# Thermistors.net
KiCad netlist of a schematic drawn in Altium Designer
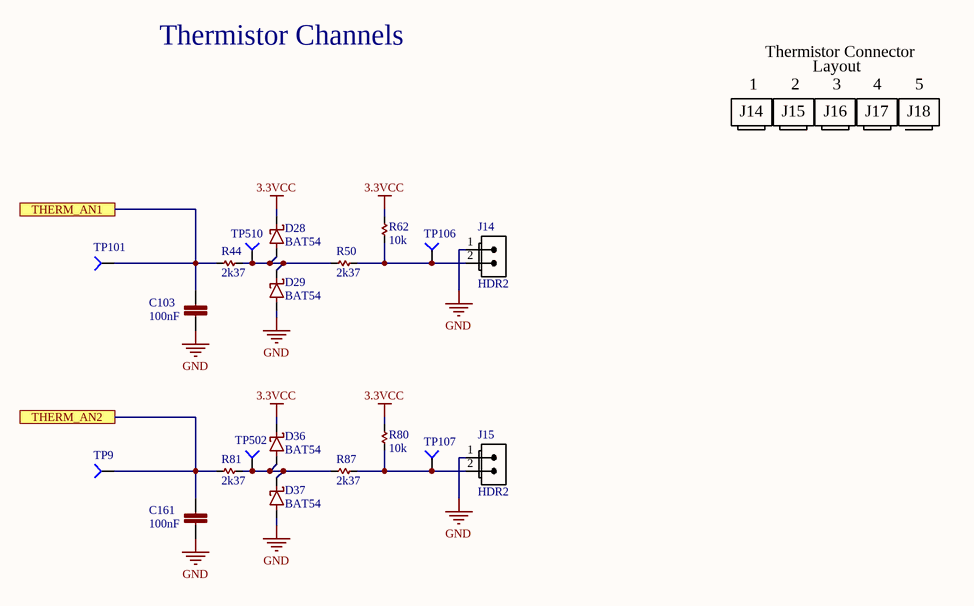
[diagram p0: Thermistors.SchDoc]

(export (version "E")
  (design (tool "Eeschema 10.0.6"))
  (components
    (comp (ref "C103")
      (value "100nF")
      (footprint "C0402")
      (description "CAP CER 0402 100nF 16V 10% X7R")
      (fields (field (name "MANUFACTURER") "Murata") (field (name "PART") "GRM155R71C104KA88D"))
      (libsource (lib "3Delight") (part "GRM155R71C104KA88D"))
    )
    (comp (ref "C161")
      (value "100nF")
      (footprint "C0402")
      (description "CAP CER 0402 100nF 16V 10% X7R")
      (fields (field (name "MANUFACTURER") "Murata") (field (name "PART") "GRM155R71C104KA88D"))
      (libsource (lib "3Delight") (part "GRM155R71C104KA88D"))
    )
    (comp (ref "D28")
      (value "BAT54")
      (footprint "SOD523_IPC")
      (description "DIODE SCHOTTKY 30V 200MA SOD523")
      (fields (field (name "MANUFACTURER") "Diodes Incorporated") (field (name "PART") "BAT54WX-TP"))
      (libsource (lib "Diodes") (part "BAT54WX"))
    )
    (comp (ref "D29")
      (value "BAT54")
      (footprint "SOD523_IPC")
      (description "DIODE SCHOTTKY 30V 200MA SOD523")
      (fields (field (name "MANUFACTURER") "Diodes Incorporated") (field (name "PART") "BAT54WX-TP"))
      (libsource (lib "Diodes") (part "BAT54WX"))
    )
    (comp (ref "D36")
      (value "BAT54")
      (footprint "SOD523_IPC")
      (description "DIODE SCHOTTKY 30V 200MA SOD523")
      (fields (field (name "MANUFACTURER") "Diodes Incorporated") (field (name "PART") "BAT54WX-TP"))
      (libsource (lib "Diodes") (part "BAT54WX"))
    )
    (comp (ref "D37")
      (value "BAT54")
      (footprint "SOD523_IPC")
      (description "DIODE SCHOTTKY 30V 200MA SOD523")
      (fields (field (name "MANUFACTURER") "Diodes Incorporated") (field (name "PART") "BAT54WX-TP"))
      (libsource (lib "Diodes") (part "BAT54WX"))
    )
    (comp (ref "J14")
      (value "HDR2")
      (footprint "70543-01 PIN-IN-PASTE")
      (description "Connector 2pos - Pin in Paste")
      (fields (field (name "MANUFACTURER") "Molex") (field (name "PART") "0705430001"))
      (libsource (lib "Connectors") (part "CONN 2PIN VERT 0.1{dblquote} SHRD LOCKING PIP"))
    )
    (comp (ref "J15")
      (value "HDR2")
      (footprint "70543-01 PIN-IN-PASTE")
      (description "Connector 2pos - Pin in Paste")
      (fields (field (name "MANUFACTURER") "Molex") (field (name "PART") "0705430001"))
      (libsource (lib "Connectors") (part "CONN 2PIN VERT 0.1{dblquote} SHRD LOCKING PIP"))
    )
    (comp (ref "R44")
      (value "2k37")
      (footprint "R0402")
      (description "RES SMD 2.37K OHM 1% 1/16W 0402")
      (fields (field (name "MANUFACTURER") "Yageo") (field (name "PART") "RC0402FR-072K37L"))
      (libsource (lib "3Delight") (part "RC0402FR-072K37L"))
    )
    (comp (ref "R50")
      (value "2k37")
      (footprint "R0402")
      (description "RES SMD 2.37K OHM 1% 1/16W 0402")
      (fields (field (name "MANUFACTURER") "Yageo") (field (name "PART") "RC0402FR-072K37L"))
      (libsource (lib "3Delight") (part "RC0402FR-072K37L"))
    )
    (comp (ref "R62")
      (value "10k")
      (footprint "R0402")
      (description "RES SMD 4.7K OHM 1% 1/16W 0402")
      (fields (field (name "MANUFACTURER") "YAGEO") (field (name "PART") "RC0402FR-074K7L"))
      (libsource (lib "3Delight") (part "RC0402FR-074K7L"))
    )
    (comp (ref "R80")
      (value "10k")
      (footprint "R0402")
      (description "RES SMD 4.7K OHM 1% 1/16W 0402")
      (fields (field (name "MANUFACTURER") "YAGEO") (field (name "PART") "RC0402FR-074K7L"))
      (libsource (lib "3Delight") (part "RC0402FR-074K7L"))
    )
    (comp (ref "R81")
      (value "2k37")
      (footprint "R0402")
      (description "RES SMD 2.37K OHM 1% 1/16W 0402")
      (fields (field (name "MANUFACTURER") "Yageo") (field (name "PART") "RC0402FR-072K37L"))
      (libsource (lib "3Delight") (part "RC0402FR-072K37L"))
    )
    (comp (ref "R87")
      (value "2k37")
      (footprint "R0402")
      (description "RES SMD 2.37K OHM 1% 1/16W 0402")
      (fields (field (name "MANUFACTURER") "Yageo") (field (name "PART") "RC0402FR-072K37L"))
      (libsource (lib "3Delight") (part "RC0402FR-072K37L"))
    )
    (comp (ref "TP9")
      (value "TP4")
      (footprint "TP-2")
      (description "Socket")
      (fields (field (name "PART") "NOTAPART-Testpoint"))
      (libsource (lib "Archim") (part "Socket"))
    )
    (comp (ref "TP101")
      (value "TP4")
      (footprint "TP-2")
      (description "Socket")
      (fields (field (name "PART") "NOTAPART-Testpoint"))
      (libsource (lib "Archim") (part "Socket"))
    )
    (comp (ref "TP106")
      (value "TP4")
      (footprint "TP-2")
      (description "Socket")
      (fields (field (name "PART") "NOTAPART-Testpoint"))
      (libsource (lib "Archim") (part "Socket"))
    )
    (comp (ref "TP107")
      (value "TP4")
      (footprint "TP-2")
      (description "Socket")
      (fields (field (name "PART") "NOTAPART-Testpoint"))
      (libsource (lib "Archim") (part "Socket"))
    )
    (comp (ref "TP502")
      (value "TP4")
      (footprint "TP-2")
      (description "Socket")
      (fields (field (name "PART") "NOTAPART-Testpoint"))
      (libsource (lib "Archim") (part "Socket"))
    )
    (comp (ref "TP510")
      (value "TP4")
      (footprint "TP-2")
      (description "Socket")
      (fields (field (name "PART") "NOTAPART-Testpoint"))
      (libsource (lib "Archim") (part "Socket"))
    )
  )
  (nets
    (net (code "1") (name "/THERM_AN1") (class "Default")
      (node (ref "C103") (pin "1") (pinfunction "1_1") (pintype "passive"))
      (node (ref "R44") (pin "1") (pinfunction "1_1") (pintype "passive"))
      (node (ref "TP101") (pin "1") (pinfunction "1_1") (pintype "passive"))
    )
    (net (code "2") (name "/THERM_AN2") (class "Default")
      (node (ref "C161") (pin "1") (pinfunction "1_1") (pintype "passive"))
      (node (ref "R81") (pin "1") (pinfunction "1_1") (pintype "passive"))
      (node (ref "TP9") (pin "1") (pinfunction "1_1") (pintype "passive"))
    )
    (net (code "3") (name "3.3VCC") (class "Default")
      (node (ref "D28") (pin "K") (pinfunction "K_K") (pintype "passive"))
      (node (ref "D36") (pin "K") (pinfunction "K_K") (pintype "passive"))
      (node (ref "R62") (pin "2") (pinfunction "2_2") (pintype "passive"))
      (node (ref "R80") (pin "2") (pinfunction "2_2") (pintype "passive"))
    )
    (net (code "4") (name "GND") (class "Default")
      (node (ref "C103") (pin "2") (pinfunction "2_2") (pintype "passive"))
      (node (ref "C161") (pin "2") (pinfunction "2_2") (pintype "passive"))
      (node (ref "D29") (pin "A") (pinfunction "A_A") (pintype "passive"))
      (node (ref "D37") (pin "A") (pinfunction "A_A") (pintype "passive"))
      (node (ref "J14") (pin "1") (pinfunction "S_1") (pintype "passive"))
      (node (ref "J15") (pin "1") (pinfunction "S_1") (pintype "passive"))
    )
    (net (code "5") (name "Net-(D28-PadA)") (class "Default")
      (node (ref "D28") (pin "A") (pinfunction "A_A") (pintype "passive"))
      (node (ref "D29") (pin "K") (pinfunction "K_K") (pintype "passive"))
      (node (ref "R44") (pin "2") (pinfunction "2_2") (pintype "passive"))
      (node (ref "R50") (pin "1") (pinfunction "1_1") (pintype "passive"))
      (node (ref "TP510") (pin "1") (pinfunction "1_1") (pintype "passive"))
    )
    (net (code "6") (name "Net-(D36-PadA)") (class "Default")
      (node (ref "D36") (pin "A") (pinfunction "A_A") (pintype "passive"))
      (node (ref "D37") (pin "K") (pinfunction "K_K") (pintype "passive"))
      (node (ref "R81") (pin "2") (pinfunction "2_2") (pintype "passive"))
      (node (ref "R87") (pin "1") (pinfunction "1_1") (pintype "passive"))
      (node (ref "TP502") (pin "1") (pinfunction "1_1") (pintype "passive"))
    )
    (net (code "7") (name "Net-(J14-S-Pad2)") (class "Default")
      (node (ref "J14") (pin "2") (pinfunction "S_2") (pintype "passive"))
      (node (ref "R50") (pin "2") (pinfunction "2_2") (pintype "passive"))
      (node (ref "R62") (pin "1") (pinfunction "1_1") (pintype "passive"))
      (node (ref "TP106") (pin "1") (pinfunction "1_1") (pintype "passive"))
    )
    (net (code "8") (name "Net-(J15-S-Pad2)") (class "Default")
      (node (ref "J15") (pin "2") (pinfunction "S_2") (pintype "passive"))
      (node (ref "R80") (pin "1") (pinfunction "1_1") (pintype "passive"))
      (node (ref "R87") (pin "2") (pinfunction "2_2") (pintype "passive"))
      (node (ref "TP107") (pin "1") (pinfunction "1_1") (pintype "passive"))
    )
  )
)
